# LFFF.net
KiCad netlist of a schematic drawn in Altium Designer
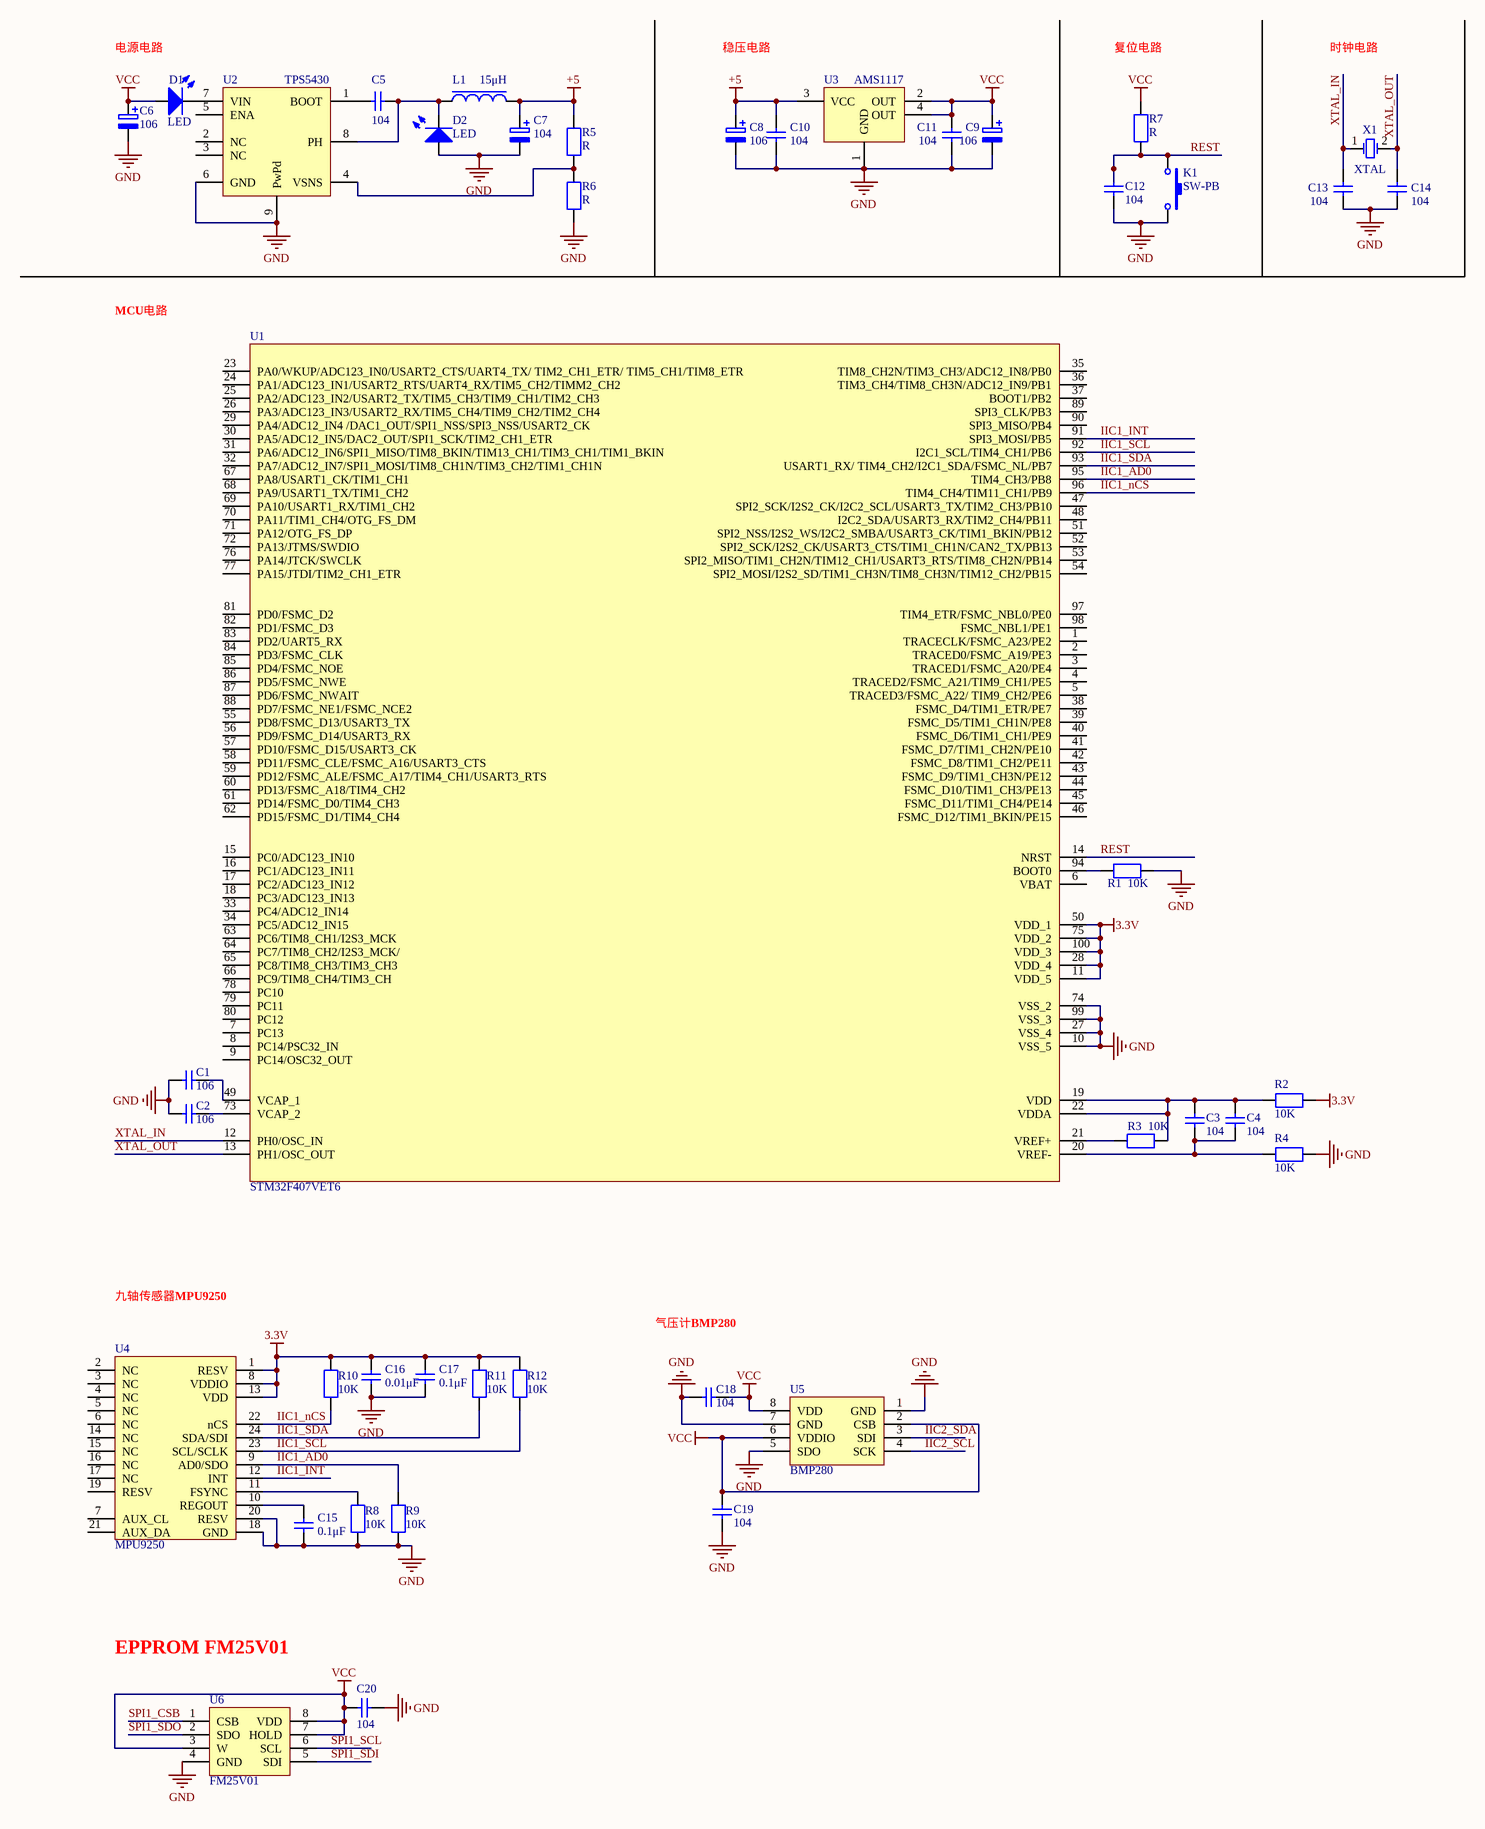
[diagram p0: LFFF.SchDoc]

(export (version "E")
  (design (tool "Eeschema 10.0.6"))
  (components
    (comp (ref "C1") (value "106") (footprint "RC0805") (libsource (lib "LFIF") (part "C")))
    (comp (ref "C2") (value "106") (footprint "RC0805") (libsource (lib "LFIF") (part "C")))
    (comp (ref "C3") (value "104") (footprint "RC0805") (libsource (lib "LFIF") (part "C")))
    (comp (ref "C4") (value "104") (footprint "RC0805") (libsource (lib "LFIF") (part "C")))
    (comp (ref "C5") (value "104") (footprint "RC0805") (libsource (lib "LFIF") (part "C")))
    (comp (ref "C6") (value "106") (footprint "RC0805") (libsource (lib "LFIF") (part "C pol")))
    (comp (ref "C7") (value "104") (footprint "RC0805") (libsource (lib "LFIF") (part "C pol")))
    (comp (ref "C8") (value "106") (footprint "RC0805") (libsource (lib "LFIF") (part "C pol")))
    (comp (ref "C9") (value "106") (footprint "RC0805") (libsource (lib "LFIF") (part "C pol")))
    (comp (ref "C10") (value "104") (footprint "RC0805") (libsource (lib "LFIF") (part "C")))
    (comp (ref "C11") (value "104") (footprint "RC0805") (libsource (lib "LFIF") (part "C")))
    (comp (ref "C12") (value "104") (footprint "RC0805") (libsource (lib "LFIF") (part "C")))
    (comp (ref "C13") (value "104") (footprint "RC0805") (libsource (lib "LFIF") (part "C")))
    (comp (ref "C14") (value "104") (footprint "RC0805") (libsource (lib "LFIF") (part "C")))
    (comp (ref "C15") (value "0.1μF") (footprint "RC0805") (libsource (lib "LFIF") (part "C")))
    (comp (ref "C16") (value "0.01μF") (footprint "RC0805") (libsource (lib "LFIF") (part "C")))
    (comp (ref "C17") (value "0.1μF") (footprint "RC0805") (libsource (lib "LFIF") (part "C")))
    (comp (ref "C18") (value "104") (footprint "RC0805") (libsource (lib "LFIF") (part "C")))
    (comp (ref "C19") (value "104") (footprint "RC0805") (libsource (lib "LFIF") (part "C")))
    (comp (ref "C20") (value "104") (footprint "RC0805") (libsource (lib "LFIF") (part "C")))
    (comp (ref "D1") (value "LED") (footprint "LED") (libsource (lib "LFIF") (part "LED")))
    (comp (ref "D2") (value "LED") (footprint "LED") (libsource (lib "LFIF") (part "LED")))
    (comp (ref "K1") (value "SW-PB") (footprint "SW-PB") (libsource (lib "LFIF") (part "SW-PB")))
    (comp (ref "L1") (value "15μH") (footprint "CD45") (libsource (lib "LFIF") (part "L")))
    (comp (ref "R1") (value "10K") (footprint "RC0805") (libsource (lib "LFIF") (part "R")))
    (comp (ref "R2") (value "10K") (footprint "RC0805") (libsource (lib "LFIF") (part "R")))
    (comp (ref "R3") (value "10K") (footprint "RC0805") (libsource (lib "LFIF") (part "R")))
    (comp (ref "R4") (value "10K") (footprint "RC0805") (libsource (lib "LFIF") (part "R")))
    (comp (ref "R5") (value "R") (footprint "RC0805") (libsource (lib "LFIF") (part "R")))
    (comp (ref "R6") (value "R") (footprint "RC0805") (libsource (lib "LFIF") (part "R")))
    (comp (ref "R7") (value "R") (footprint "RC0805") (libsource (lib "LFIF") (part "R")))
    (comp (ref "R8") (value "10K") (footprint "RC0805") (libsource (lib "LFIF") (part "R")))
    (comp (ref "R9") (value "10K") (footprint "RC0805") (libsource (lib "LFIF") (part "R")))
    (comp (ref "R10") (value "10K") (footprint "RC0805") (libsource (lib "LFIF") (part "R")))
    (comp (ref "R11") (value "10K") (footprint "RC0805") (libsource (lib "LFIF") (part "R")))
    (comp (ref "R12") (value "10K") (footprint "RC0805") (libsource (lib "LFIF") (part "R")))
    (comp (ref "U1")
      (value "STM32F407VET6")
      (footprint "STM32F407VET6")
      (libsource (lib "LFIF") (part "STM32F407VET6"))
    )
    (comp (ref "U2") (value "TPS5430") (footprint "TPS5430") (libsource (lib "LFIF") (part "TPS5430")))
    (comp (ref "U3") (value "AMS1117") (footprint "AMS1117") (libsource (lib "LFIF") (part "AMS1117")))
    (comp (ref "U4") (value "MPU9250") (footprint "MPU9250") (libsource (lib "LFIF") (part "MPU9250")))
    (comp (ref "U5") (value "BMP280") (libsource (lib "LFIF") (part "BMP280")))
    (comp (ref "U6") (value "FM25V01") (footprint "FM25V01") (libsource (lib "LFIF") (part "FM25V01")))
    (comp (ref "X1") (value "XTAL") (footprint "49S-SMD") (libsource (lib "LFIF") (part "XTAL")))
  )
  (nets
    (net (code "1") (name "+5") (class "Default")
      (node (ref "C10") (pin "1") (pintype "passive"))
      (node (ref "C7") (pin "1") (pintype "passive"))
      (node (ref "C8") (pin "1") (pintype "passive"))
      (node (ref "L1") (pin "2") (pintype "passive"))
      (node (ref "R5") (pin "2") (pintype "passive"))
      (node (ref "U3") (pin "3") (pinfunction "VCC_3") (pintype "passive"))
    )
    (net (code "2") (name "/IIC1_AD0") (class "Default")
      (node (ref "R9") (pin "2") (pintype "passive"))
      (node (ref "U1") (pin "95") (pinfunction "TIM4_CH3/PB8_95") (pintype "passive"))
      (node (ref "U4") (pin "9") (pinfunction "AD0/SDO_9") (pintype "passive"))
    )
    (net (code "3") (name "/IIC1_INT") (class "Default")
      (node (ref "U1") (pin "91") (pinfunction "SPI3_MOSI/PB5_91") (pintype "passive"))
      (node (ref "U4") (pin "12") (pinfunction "INT_12") (pintype "passive"))
    )
    (net (code "4") (name "/IIC1_SCL") (class "Default")
      (node (ref "R12") (pin "1") (pintype "passive"))
      (node (ref "U1") (pin "92") (pinfunction "I2C1_SCL/TIM4_CH1/PB6_92") (pintype "passive"))
      (node (ref "U4") (pin "23") (pinfunction "SCL/SCLK_23") (pintype "passive"))
    )
    (net (code "5") (name "/IIC1_SDA") (class "Default")
      (node (ref "R11") (pin "1") (pintype "passive"))
      (node (ref "U1") (pin "93") (pinfunction "USART1_RX/_TIM4_CH2/I2C1_SDA/FSMC_NL/PB7_93") (pintype "passive"))
      (node (ref "U4") (pin "24") (pinfunction "SDA/SDI_24") (pintype "passive"))
    )
    (net (code "6") (name "/IIC1_nCS") (class "Default")
      (node (ref "R10") (pin "1") (pintype "passive"))
      (node (ref "U1") (pin "96") (pinfunction "TIM4_CH4/TIM11_CH1/PB9_96") (pintype "passive"))
      (node (ref "U4") (pin "22") (pinfunction "nCS_22") (pintype "passive"))
    )
    (net (code "7") (name "/IIC2_SCL") (class "Default")
      (node (ref "U5") (pin "4") (pinfunction "SCK_4") (pintype "passive"))
    )
    (net (code "8") (name "/IIC2_SDA") (class "Default")
      (node (ref "U5") (pin "3") (pinfunction "SDI_3") (pintype "passive"))
    )
    (net (code "9") (name "/REST") (class "Default")
      (node (ref "C12") (pin "2") (pintype "passive"))
      (node (ref "K1") (pin "1") (pintype "passive"))
      (node (ref "R7") (pin "1") (pintype "passive"))
      (node (ref "U1") (pin "14") (pinfunction "NRST_14") (pintype "passive"))
    )
    (net (code "10") (name "/SPI1_CSB") (class "Default")
      (node (ref "U6") (pin "1") (pinfunction "CSB_1") (pintype "passive"))
    )
    (net (code "11") (name "/SPI1_SCL") (class "Default")
      (node (ref "U6") (pin "6") (pinfunction "SCL_6") (pintype "passive"))
    )
    (net (code "12") (name "/SPI1_SDI") (class "Default")
      (node (ref "U6") (pin "5") (pinfunction "SDI_5") (pintype "passive"))
    )
    (net (code "13") (name "/SPI1_SDO") (class "Default")
      (node (ref "U6") (pin "2") (pinfunction "SDO_2") (pintype "passive"))
    )
    (net (code "14") (name "/XTAL_IN") (class "Default")
      (node (ref "C13") (pin "2") (pintype "passive"))
      (node (ref "U1") (pin "12") (pinfunction "PH0/OSC_IN_12") (pintype "passive"))
      (node (ref "X1") (pin "1") (pinfunction "IN_1") (pintype "passive"))
    )
    (net (code "15") (name "/XTAL_OUT") (class "Default")
      (node (ref "C14") (pin "2") (pintype "passive"))
      (node (ref "U1") (pin "13") (pinfunction "PH1/OSC_OUT_13") (pintype "passive"))
      (node (ref "X1") (pin "2") (pinfunction "OUT_2") (pintype "passive"))
    )
    (net (code "16") (name "3.3V") (class "Default")
      (node (ref "C16") (pin "2") (pintype "passive"))
      (node (ref "C17") (pin "2") (pintype "passive"))
      (node (ref "R10") (pin "2") (pintype "passive"))
      (node (ref "R11") (pin "2") (pintype "passive"))
      (node (ref "R12") (pin "2") (pintype "passive"))
      (node (ref "R2") (pin "2") (pintype "passive"))
      (node (ref "U1") (pin "100") (pinfunction "VDD_3_100") (pintype "passive"))
      (node (ref "U1") (pin "11") (pinfunction "VDD_5_11") (pintype "passive"))
      (node (ref "U1") (pin "28") (pinfunction "VDD_4_28") (pintype "passive"))
      (node (ref "U1") (pin "50") (pinfunction "VDD_1_50") (pintype "passive"))
      (node (ref "U1") (pin "75") (pinfunction "VDD_2_75") (pintype "passive"))
      (node (ref "U4") (pin "1") (pinfunction "RESV_1") (pintype "passive"))
      (node (ref "U4") (pin "13") (pinfunction "VDD_13") (pintype "passive"))
      (node (ref "U4") (pin "8") (pinfunction "VDDIO_8") (pintype "passive"))
    )
    (net (code "17") (name "GND") (class "Default")
      (node (ref "C1") (pin "1") (pintype "passive"))
      (node (ref "C10") (pin "2") (pintype "passive"))
      (node (ref "C11") (pin "2") (pintype "passive"))
      (node (ref "C12") (pin "1") (pintype "passive"))
      (node (ref "C13") (pin "1") (pintype "passive"))
      (node (ref "C14") (pin "1") (pintype "passive"))
      (node (ref "C15") (pin "1") (pintype "passive"))
      (node (ref "C16") (pin "1") (pintype "passive"))
      (node (ref "C17") (pin "1") (pintype "passive"))
      (node (ref "C18") (pin "1") (pintype "passive"))
      (node (ref "C19") (pin "1") (pintype "passive"))
      (node (ref "C2") (pin "1") (pintype "passive"))
      (node (ref "C20") (pin "2") (pintype "passive"))
      (node (ref "C6") (pin "2") (pintype "passive"))
      (node (ref "C7") (pin "2") (pintype "passive"))
      (node (ref "C8") (pin "2") (pintype "passive"))
      (node (ref "C9") (pin "2") (pintype "passive"))
      (node (ref "D2") (pin "1") (pintype "passive"))
      (node (ref "K1") (pin "2") (pintype "passive"))
      (node (ref "R1") (pin "2") (pintype "passive"))
      (node (ref "R4") (pin "2") (pintype "passive"))
      (node (ref "R6") (pin "1") (pintype "passive"))
      (node (ref "R8") (pin "1") (pintype "passive"))
      (node (ref "R9") (pin "1") (pintype "passive"))
      (node (ref "U1") (pin "10") (pinfunction "VSS_5_10") (pintype "passive"))
      (node (ref "U1") (pin "27") (pinfunction "VSS_4_27") (pintype "passive"))
      (node (ref "U1") (pin "74") (pinfunction "VSS_2_74") (pintype "passive"))
      (node (ref "U1") (pin "99") (pinfunction "VSS_3_99") (pintype "passive"))
      (node (ref "U2") (pin "6") (pinfunction "GND_6") (pintype "passive"))
      (node (ref "U2") (pin "9") (pinfunction "PwPd_9") (pintype "passive"))
      (node (ref "U3") (pin "1") (pinfunction "GND_1") (pintype "passive"))
      (node (ref "U4") (pin "18") (pinfunction "GND_18") (pintype "passive"))
      (node (ref "U4") (pin "20") (pinfunction "RESV_20") (pintype "passive"))
      (node (ref "U5") (pin "1") (pinfunction "GND_1") (pintype "passive"))
      (node (ref "U5") (pin "5") (pinfunction "SDO_5") (pintype "passive"))
      (node (ref "U5") (pin "7") (pinfunction "GND_7") (pintype "passive"))
      (node (ref "U6") (pin "4") (pinfunction "GND_4") (pintype "passive"))
    )
    (net (code "18") (name "Net-(U1-BOOT0)") (class "Default")
      (node (ref "R1") (pin "1") (pintype "passive"))
      (node (ref "U1") (pin "94") (pinfunction "BOOT0_94") (pintype "passive"))
    )
    (net (code "19") (name "Net-(U1-VCAP_1)") (class "Default")
      (node (ref "C1") (pin "2") (pintype "passive"))
      (node (ref "U1") (pin "49") (pinfunction "VCAP_1_49") (pintype "passive"))
    )
    (net (code "20") (name "Net-(U1-VCAP_2)") (class "Default")
      (node (ref "C2") (pin "2") (pintype "passive"))
      (node (ref "U1") (pin "73") (pinfunction "VCAP_2_73") (pintype "passive"))
    )
    (net (code "21") (name "Net-(U1-VDD)") (class "Default")
      (node (ref "C3") (pin "2") (pintype "passive"))
      (node (ref "C4") (pin "2") (pintype "passive"))
      (node (ref "R2") (pin "1") (pintype "passive"))
      (node (ref "R3") (pin "2") (pintype "passive"))
      (node (ref "U1") (pin "19") (pinfunction "VDD_19") (pintype "passive"))
      (node (ref "U1") (pin "22") (pinfunction "VDDA_22") (pintype "passive"))
    )
    (net (code "22") (name "Net-(U1-VREF+)") (class "Default")
      (node (ref "R3") (pin "1") (pintype "passive"))
      (node (ref "U1") (pin "21") (pinfunction "VREF+_21") (pintype "passive"))
    )
    (net (code "23") (name "Net-(U1-VREF-)") (class "Default")
      (node (ref "C3") (pin "1") (pintype "passive"))
      (node (ref "C4") (pin "1") (pintype "passive"))
      (node (ref "R4") (pin "1") (pintype "passive"))
      (node (ref "U1") (pin "20") (pinfunction "VREF-_20") (pintype "passive"))
    )
    (net (code "24") (name "Net-(U2-BOOT)") (class "Default")
      (node (ref "C5") (pin "1") (pintype "passive"))
      (node (ref "U2") (pin "1") (pinfunction "BOOT_1") (pintype "passive"))
    )
    (net (code "25") (name "Net-(U2-PH)") (class "Default")
      (node (ref "C5") (pin "2") (pintype "passive"))
      (node (ref "D2") (pin "2") (pintype "passive"))
      (node (ref "L1") (pin "1") (pintype "passive"))
      (node (ref "U2") (pin "8") (pinfunction "PH_8") (pintype "passive"))
    )
    (net (code "26") (name "Net-(U2-VIN)") (class "Default")
      (node (ref "D1") (pin "2") (pintype "passive"))
      (node (ref "U2") (pin "7") (pinfunction "VIN_7") (pintype "passive"))
    )
    (net (code "27") (name "Net-(U2-VSNS)") (class "Default")
      (node (ref "R5") (pin "1") (pintype "passive"))
      (node (ref "R6") (pin "2") (pintype "passive"))
      (node (ref "U2") (pin "4") (pinfunction "VSNS_4") (pintype "passive"))
    )
    (net (code "28") (name "Net-(U4-FSYNC)") (class "Default")
      (node (ref "R8") (pin "2") (pintype "passive"))
      (node (ref "U4") (pin "11") (pinfunction "FSYNC_11") (pintype "passive"))
    )
    (net (code "29") (name "Net-(U4-REGOUT)") (class "Default")
      (node (ref "C15") (pin "2") (pintype "passive"))
      (node (ref "U4") (pin "10") (pinfunction "REGOUT_10") (pintype "passive"))
    )
    (net (code "30") (name "VCC") (class "Default")
      (node (ref "C11") (pin "1") (pintype "passive"))
      (node (ref "C18") (pin "2") (pintype "passive"))
      (node (ref "C19") (pin "2") (pintype "passive"))
      (node (ref "C20") (pin "1") (pintype "passive"))
      (node (ref "C6") (pin "1") (pintype "passive"))
      (node (ref "C9") (pin "1") (pintype "passive"))
      (node (ref "D1") (pin "1") (pintype "passive"))
      (node (ref "R7") (pin "2") (pintype "passive"))
      (node (ref "U3") (pin "2") (pinfunction "OUT_2") (pintype "passive"))
      (node (ref "U3") (pin "4") (pinfunction "OUT_4") (pintype "passive"))
      (node (ref "U5") (pin "2") (pinfunction "CSB_2") (pintype "passive"))
      (node (ref "U5") (pin "6") (pinfunction "VDDIO_6") (pintype "passive"))
      (node (ref "U5") (pin "8") (pinfunction "VDD_8") (pintype "passive"))
      (node (ref "U6") (pin "3") (pinfunction "W_3") (pintype "passive"))
      (node (ref "U6") (pin "7") (pinfunction "HOLD_7") (pintype "passive"))
      (node (ref "U6") (pin "8") (pinfunction "VDD_8") (pintype "passive"))
    )
    (net (code "31") (name "unconnected-(U1-BOOT1{slash}PB2-Pad37)") (class "Default")
      (node (ref "U1") (pin "37") (pinfunction "BOOT1/PB2_37") (pintype "passive"))
    )
    (net (code "32") (name "unconnected-(U1-FSMC_D4{slash}TIM1_ETR{slash}PE7-Pad38)") (class "Default")
      (node (ref "U1") (pin "38") (pinfunction "FSMC_D4/TIM1_ETR/PE7_38") (pintype "passive"))
    )
    (net (code "33") (name "unconnected-(U1-FSMC_D5{slash}TIM1_CH1N{slash}PE8-Pad39)") (class "Default")
      (node (ref "U1") (pin "39") (pinfunction "FSMC_D5/TIM1_CH1N/PE8_39") (pintype "passive"))
    )
    (net (code "34") (name "unconnected-(U1-FSMC_D6{slash}TIM1_CH1{slash}PE9-Pad40)") (class "Default")
      (node (ref "U1") (pin "40") (pinfunction "FSMC_D6/TIM1_CH1/PE9_40") (pintype "passive"))
    )
    (net (code "35") (name "unconnected-(U1-FSMC_D7{slash}TIM1_CH2N{slash}PE10-Pad41)") (class "Default")
      (node (ref "U1") (pin "41") (pinfunction "FSMC_D7/TIM1_CH2N/PE10_41") (pintype "passive"))
    )
    (net (code "36") (name "unconnected-(U1-FSMC_D8{slash}TIM1_CH2{slash}PE11-Pad42)") (class "Default")
      (node (ref "U1") (pin "42") (pinfunction "FSMC_D8/TIM1_CH2/PE11_42") (pintype "passive"))
    )
    (net (code "37") (name "unconnected-(U1-FSMC_D9{slash}TIM1_CH3N{slash}PE12-Pad43)") (class "Default")
      (node (ref "U1") (pin "43") (pinfunction "FSMC_D9/TIM1_CH3N/PE12_43") (pintype "passive"))
    )
    (net (code "38") (name "unconnected-(U1-FSMC_D10{slash}TIM1_CH3{slash}PE13-Pad44)") (class "Default")
      (node (ref "U1") (pin "44") (pinfunction "FSMC_D10/TIM1_CH3/PE13_44") (pintype "passive"))
    )
    (net (code "39") (name "unconnected-(U1-FSMC_D11{slash}TIM1_CH4{slash}PE14-Pad45)") (class "Default")
      (node (ref "U1") (pin "45") (pinfunction "FSMC_D11/TIM1_CH4/PE14_45") (pintype "passive"))
    )
    (net (code "40") (name "unconnected-(U1-FSMC_D12{slash}TIM1_BKIN{slash}PE15-Pad46)") (class "Default")
      (node (ref "U1") (pin "46") (pinfunction "FSMC_D12/TIM1_BKIN/PE15_46") (pintype "passive"))
    )
    (net (code "41") (name "unconnected-(U1-FSMC_NBL1{slash}PE1-Pad98)") (class "Default")
      (node (ref "U1") (pin "98") (pinfunction "FSMC_NBL1/PE1_98") (pintype "passive"))
    )
    (net (code "42") (name "unconnected-(U1-I2C2_SDA{slash}USART3_RX{slash}TIM2_CH4{slash}PB11-Pad48)") (class "Default")
      (node (ref "U1") (pin "48") (pinfunction "I2C2_SDA/USART3_RX/TIM2_CH4/PB11_48") (pintype "passive"))
    )
    (net (code "43") (name "unconnected-(U1-PA0{slash}WKUP{slash}ADC123_IN0{slash}USART2_CTS{slash}UART4_TX{slash}_TIM2_CH1_ETR{slash}_TIM5_CH1{slash}TIM8_ETR-Pad23)") (class "Default")
      (node (ref "U1") (pin "23") (pinfunction "PA0/WKUP/ADC123_IN0/USART2_CTS/UART4_TX/_TIM2_CH1_ETR/_TIM5_CH1/TIM8_ETR_23") (pintype "passive"))
    )
    (net (code "44") (name "unconnected-(U1-PA1{slash}ADC123_IN1{slash}USART2_RTS{slash}UART4_RX{slash}TIM5_CH2{slash}TIMM2_CH2-Pad24)") (class "Default")
      (node (ref "U1") (pin "24") (pinfunction "PA1/ADC123_IN1/USART2_RTS/UART4_RX/TIM5_CH2/TIMM2_CH2_24") (pintype "passive"))
    )
    (net (code "45") (name "unconnected-(U1-PA2{slash}ADC123_IN2{slash}USART2_TX{slash}TIM5_CH3{slash}TIM9_CH1{slash}TIM2_CH3-Pad25)") (class "Default")
      (node (ref "U1") (pin "25") (pinfunction "PA2/ADC123_IN2/USART2_TX/TIM5_CH3/TIM9_CH1/TIM2_CH3_25") (pintype "passive"))
    )
    (net (code "46") (name "unconnected-(U1-PA3{slash}ADC123_IN3{slash}USART2_RX{slash}TIM5_CH4{slash}TIM9_CH2{slash}TIM2_CH4-Pad26)") (class "Default")
      (node (ref "U1") (pin "26") (pinfunction "PA3/ADC123_IN3/USART2_RX/TIM5_CH4/TIM9_CH2/TIM2_CH4_26") (pintype "passive"))
    )
    (net (code "47") (name "unconnected-(U1-PA4{slash}ADC12_IN4_{slash}DAC1_OUT{slash}SPI1_NSS{slash}SPI3_NSS{slash}USART2_CK-Pad29)") (class "Default")
      (node (ref "U1") (pin "29") (pinfunction "PA4/ADC12_IN4_/DAC1_OUT/SPI1_NSS/SPI3_NSS/USART2_CK_29") (pintype "passive"))
    )
    (net (code "48") (name "unconnected-(U1-PA5{slash}ADC12_IN5{slash}DAC2_OUT{slash}SPI1_SCK{slash}TIM2_CH1_ETR-Pad30)") (class "Default")
      (node (ref "U1") (pin "30") (pinfunction "PA5/ADC12_IN5/DAC2_OUT/SPI1_SCK/TIM2_CH1_ETR_30") (pintype "passive"))
    )
    (net (code "49") (name "unconnected-(U1-PA6{slash}ADC12_IN6{slash}SPI1_MISO{slash}TIM8_BKIN{slash}TIM13_CH1{slash}TIM3_CH1{slash}TIM1_BKIN-Pad31)") (class "Default")
      (node (ref "U1") (pin "31") (pinfunction "PA6/ADC12_IN6/SPI1_MISO/TIM8_BKIN/TIM13_CH1/TIM3_CH1/TIM1_BKIN_31") (pintype "passive"))
    )
    (net (code "50") (name "unconnected-(U1-PA7{slash}ADC12_IN7{slash}SPI1_MOSI{slash}TIM8_CH1N{slash}TIM3_CH2{slash}TIM1_CH1N-Pad32)") (class "Default")
      (node (ref "U1") (pin "32") (pinfunction "PA7/ADC12_IN7/SPI1_MOSI/TIM8_CH1N/TIM3_CH2/TIM1_CH1N_32") (pintype "passive"))
    )
    (net (code "51") (name "unconnected-(U1-PA8{slash}USART1_CK{slash}TIM1_CH1-Pad67)") (class "Default")
      (node (ref "U1") (pin "67") (pinfunction "PA8/USART1_CK/TIM1_CH1_67") (pintype "passive"))
    )
    (net (code "52") (name "unconnected-(U1-PA9{slash}USART1_TX{slash}TIM1_CH2-Pad68)") (class "Default")
      (node (ref "U1") (pin "68") (pinfunction "PA9/USART1_TX/TIM1_CH2_68") (pintype "passive"))
    )
    (net (code "53") (name "unconnected-(U1-PA10{slash}USART1_RX{slash}TIM1_CH2-Pad69)") (class "Default")
      (node (ref "U1") (pin "69") (pinfunction "PA10/USART1_RX/TIM1_CH2_69") (pintype "passive"))
    )
    (net (code "54") (name "unconnected-(U1-PA11{slash}TIM1_CH4{slash}OTG_FS_DM-Pad70)") (class "Default")
      (node (ref "U1") (pin "70") (pinfunction "PA11/TIM1_CH4/OTG_FS_DM_70") (pintype "passive"))
    )
    (net (code "55") (name "unconnected-(U1-PA12{slash}OTG_FS_DP-Pad71)") (class "Default")
      (node (ref "U1") (pin "71") (pinfunction "PA12/OTG_FS_DP_71") (pintype "passive"))
    )
    (net (code "56") (name "unconnected-(U1-PA13{slash}JTMS{slash}SWDIO-Pad72)") (class "Default")
      (node (ref "U1") (pin "72") (pinfunction "PA13/JTMS/SWDIO_72") (pintype "passive"))
    )
    (net (code "57") (name "unconnected-(U1-PA14{slash}JTCK{slash}SWCLK-Pad76)") (class "Default")
      (node (ref "U1") (pin "76") (pinfunction "PA14/JTCK/SWCLK_76") (pintype "passive"))
    )
    (net (code "58") (name "unconnected-(U1-PA15{slash}JTDI{slash}TIM2_CH1_ETR-Pad77)") (class "Default")
      (node (ref "U1") (pin "77") (pinfunction "PA15/JTDI/TIM2_CH1_ETR_77") (pintype "passive"))
    )
    (net (code "59") (name "unconnected-(U1-PC0{slash}ADC123_IN10-Pad15)") (class "Default")
      (node (ref "U1") (pin "15") (pinfunction "PC0/ADC123_IN10_15") (pintype "passive"))
    )
    (net (code "60") (name "unconnected-(U1-PC1{slash}ADC123_IN11-Pad16)") (class "Default")
      (node (ref "U1") (pin "16") (pinfunction "PC1/ADC123_IN11_16") (pintype "passive"))
    )
    (net (code "61") (name "unconnected-(U1-PC2{slash}ADC123_IN12-Pad17)") (class "Default")
      (node (ref "U1") (pin "17") (pinfunction "PC2/ADC123_IN12_17") (pintype "passive"))
    )
    (net (code "62") (name "unconnected-(U1-PC3{slash}ADC123_IN13-Pad18)") (class "Default")
      (node (ref "U1") (pin "18") (pinfunction "PC3/ADC123_IN13_18") (pintype "passive"))
    )
    (net (code "63") (name "unconnected-(U1-PC4{slash}ADC12_IN14-Pad33)") (class "Default")
      (node (ref "U1") (pin "33") (pinfunction "PC4/ADC12_IN14_33") (pintype "passive"))
    )
    (net (code "64") (name "unconnected-(U1-PC5{slash}ADC12_IN15-Pad34)") (class "Default")
      (node (ref "U1") (pin "34") (pinfunction "PC5/ADC12_IN15_34") (pintype "passive"))
    )
    (net (code "65") (name "unconnected-(U1-PC6{slash}TIM8_CH1{slash}I2S3_MCK-Pad63)") (class "Default")
      (node (ref "U1") (pin "63") (pinfunction "PC6/TIM8_CH1/I2S3_MCK_63") (pintype "passive"))
    )
    (net (code "66") (name "unconnected-(U1-PC7{slash}TIM8_CH2{slash}I2S3_MCK{slash}-Pad64)") (class "Default")
      (node (ref "U1") (pin "64") (pinfunction "PC7/TIM8_CH2/I2S3_MCK/_64") (pintype "passive"))
    )
    (net (code "67") (name "unconnected-(U1-PC8{slash}TIM8_CH3{slash}TIM3_CH3-Pad65)") (class "Default")
      (node (ref "U1") (pin "65") (pinfunction "PC8/TIM8_CH3/TIM3_CH3_65") (pintype "passive"))
    )
    (net (code "68") (name "unconnected-(U1-PC9{slash}TIM8_CH4{slash}TIM3_CH-Pad66)") (class "Default")
      (node (ref "U1") (pin "66") (pinfunction "PC9/TIM8_CH4/TIM3_CH_66") (pintype "passive"))
    )
    (net (code "69") (name "unconnected-(U1-PC10-Pad78)") (class "Default")
      (node (ref "U1") (pin "78") (pinfunction "PC10_78") (pintype "passive"))
    )
    (net (code "70") (name "unconnected-(U1-PC11-Pad79)") (class "Default")
      (node (ref "U1") (pin "79") (pinfunction "PC11_79") (pintype "passive"))
    )
    (net (code "71") (name "unconnected-(U1-PC12-Pad80)") (class "Default")
      (node (ref "U1") (pin "80") (pinfunction "PC12_80") (pintype "passive"))
    )
    (net (code "72") (name "unconnected-(U1-PC13-Pad7)") (class "Default")
      (node (ref "U1") (pin "7") (pinfunction "PC13_7") (pintype "passive"))
    )
    (net (code "73") (name "unconnected-(U1-PC14{slash}OSC32_OUT-Pad9)") (class "Default")
      (node (ref "U1") (pin "9") (pinfunction "PC14/OSC32_OUT_9") (pintype "passive"))
    )
    (net (code "74") (name "unconnected-(U1-PC14{slash}PSC32_IN-Pad8)") (class "Default")
      (node (ref "U1") (pin "8") (pinfunction "PC14/PSC32_IN_8") (pintype "passive"))
    )
    (net (code "75") (name "unconnected-(U1-PD0{slash}FSMC_D2-Pad81)") (class "Default")
      (node (ref "U1") (pin "81") (pinfunction "PD0/FSMC_D2_81") (pintype "passive"))
    )
    (net (code "76") (name "unconnected-(U1-PD1{slash}FSMC_D3-Pad82)") (class "Default")
      (node (ref "U1") (pin "82") (pinfunction "PD1/FSMC_D3_82") (pintype "passive"))
    )
    (net (code "77") (name "unconnected-(U1-PD2{slash}UART5_RX-Pad83)") (class "Default")
      (node (ref "U1") (pin "83") (pinfunction "PD2/UART5_RX_83") (pintype "passive"))
    )
    (net (code "78") (name "unconnected-(U1-PD3{slash}FSMC_CLK-Pad84)") (class "Default")
      (node (ref "U1") (pin "84") (pinfunction "PD3/FSMC_CLK_84") (pintype "passive"))
    )
    (net (code "79") (name "unconnected-(U1-PD4{slash}FSMC_NOE-Pad85)") (class "Default")
      (node (ref "U1") (pin "85") (pinfunction "PD4/FSMC_NOE_85") (pintype "passive"))
    )
    (net (code "80") (name "unconnected-(U1-PD5{slash}FSMC_NWE-Pad86)") (class "Default")
      (node (ref "U1") (pin "86") (pinfunction "PD5/FSMC_NWE_86") (pintype "passive"))
    )
    (net (code "81") (name "unconnected-(U1-PD6{slash}FSMC_NWAIT-Pad87)") (class "Default")
      (node (ref "U1") (pin "87") (pinfunction "PD6/FSMC_NWAIT_87") (pintype "passive"))
    )
    (net (code "82") (name "unconnected-(U1-PD7{slash}FSMC_NE1{slash}FSMC_NCE2-Pad88)") (class "Default")
      (node (ref "U1") (pin "88") (pinfunction "PD7/FSMC_NE1/FSMC_NCE2_88") (pintype "passive"))
    )
    (net (code "83") (name "unconnected-(U1-PD8{slash}FSMC_D13{slash}USART3_TX-Pad55)") (class "Default")
      (node (ref "U1") (pin "55") (pinfunction "PD8/FSMC_D13/USART3_TX_55") (pintype "passive"))
    )
    (net (code "84") (name "unconnected-(U1-PD9{slash}FSMC_D14{slash}USART3_RX-Pad56)") (class "Default")
      (node (ref "U1") (pin "56") (pinfunction "PD9/FSMC_D14/USART3_RX_56") (pintype "passive"))
    )
    (net (code "85") (name "unconnected-(U1-PD10{slash}FSMC_D15{slash}USART3_CK-Pad57)") (class "Default")
      (node (ref "U1") (pin "57") (pinfunction "PD10/FSMC_D15/USART3_CK_57") (pintype "passive"))
    )
    (net (code "86") (name "unconnected-(U1-PD11{slash}FSMC_CLE{slash}FSMC_A16{slash}USART3_CTS-Pad58)") (class "Default")
      (node (ref "U1") (pin "58") (pinfunction "PD11/FSMC_CLE/FSMC_A16/USART3_CTS_58") (pintype "passive"))
    )
    (net (code "87") (name "unconnected-(U1-PD12{slash}FSMC_ALE{slash}FSMC_A17{slash}TIM4_CH1{slash}USART3_RTS-Pad59)") (class "Default")
      (node (ref "U1") (pin "59") (pinfunction "PD12/FSMC_ALE/FSMC_A17/TIM4_CH1/USART3_RTS_59") (pintype "passive"))
    )
    (net (code "88") (name "unconnected-(U1-PD13{slash}FSMC_A18{slash}TIM4_CH2-Pad60)") (class "Default")
      (node (ref "U1") (pin "60") (pinfunction "PD13/FSMC_A18/TIM4_CH2_60") (pintype "passive"))
    )
    (net (code "89") (name "unconnected-(U1-PD14{slash}FSMC_D0{slash}TIM4_CH3-Pad61)") (class "Default")
      (node (ref "U1") (pin "61") (pinfunction "PD14/FSMC_D0/TIM4_CH3_61") (pintype "passive"))
    )
    (net (code "90") (name "unconnected-(U1-PD15{slash}FSMC_D1{slash}TIM4_CH4-Pad62)") (class "Default")
      (node (ref "U1") (pin "62") (pinfunction "PD15/FSMC_D1/TIM4_CH4_62") (pintype "passive"))
    )
    (net (code "91") (name "unconnected-(U1-SPI2_MISO{slash}TIM1_CH2N{slash}TIM12_CH1{slash}USART3_RTS{slash}TIM8_CH2N{slash}PB14-Pad53)") (class "Default")
      (node (ref "U1") (pin "53") (pinfunction "SPI2_MISO/TIM1_CH2N/TIM12_CH1/USART3_RTS/TIM8_CH2N/PB14_53") (pintype "passive"))
    )
    (net (code "92") (name "unconnected-(U1-SPI2_MOSI{slash}I2S2_SD{slash}TIM1_CH3N{slash}TIM8_CH3N{slash}TIM12_CH2{slash}PB15-Pad54)") (class "Default")
      (node (ref "U1") (pin "54") (pinfunction "SPI2_MOSI/I2S2_SD/TIM1_CH3N/TIM8_CH3N/TIM12_CH2/PB15_54") (pintype "passive"))
    )
    (net (code "93") (name "unconnected-(U1-SPI2_NSS{slash}I2S2_WS{slash}I2C2_SMBA{slash}USART3_CK{slash}TIM1_BKIN{slash}PB12-Pad51)") (class "Default")
      (node (ref "U1") (pin "51") (pinfunction "SPI2_NSS/I2S2_WS/I2C2_SMBA/USART3_CK/TIM1_BKIN/PB12_51") (pintype "passive"))
    )
    (net (code "94") (name "unconnected-(U1-SPI2_SCK{slash}I2S2_CK{slash}I2C2_SCL{slash}USART3_TX{slash}TIM2_CH3{slash}PB10-Pad47)") (class "Default")
      (node (ref "U1") (pin "47") (pinfunction "SPI2_SCK/I2S2_CK/I2C2_SCL/USART3_TX/TIM2_CH3/PB10_47") (pintype "passive"))
    )
    (net (code "95") (name "unconnected-(U1-SPI2_SCK{slash}I2S2_CK{slash}USART3_CTS{slash}TIM1_CH1N{slash}CAN2_TX{slash}PB13-Pad52)") (class "Default")
      (node (ref "U1") (pin "52") (pinfunction "SPI2_SCK/I2S2_CK/USART3_CTS/TIM1_CH1N/CAN2_TX/PB13_52") (pintype "passive"))
    )
    (net (code "96") (name "unconnected-(U1-SPI3_CLK{slash}PB3-Pad89)") (class "Default")
      (node (ref "U1") (pin "89") (pinfunction "SPI3_CLK/PB3_89") (pintype "passive"))
    )
    (net (code "97") (name "unconnected-(U1-SPI3_MISO{slash}PB4-Pad90)") (class "Default")
      (node (ref "U1") (pin "90") (pinfunction "SPI3_MISO/PB4_90") (pintype "passive"))
    )
    (net (code "98") (name "unconnected-(U1-TIM3_CH4{slash}TIM8_CH3N{slash}ADC12_IN9{slash}PB1-Pad36)") (class "Default")
      (node (ref "U1") (pin "36") (pinfunction "TIM3_CH4/TIM8_CH3N/ADC12_IN9/PB1_36") (pintype "passive"))
    )
    (net (code "99") (name "unconnected-(U1-TIM4_ETR{slash}FSMC_NBL0{slash}PE0-Pad97)") (class "Default")
      (node (ref "U1") (pin "97") (pinfunction "TIM4_ETR/FSMC_NBL0/PE0_97") (pintype "passive"))
    )
    (net (code "100") (name "unconnected-(U1-TIM8_CH2N{slash}TIM3_CH3{slash}ADC12_IN8{slash}PB0-Pad35)") (class "Default")
      (node (ref "U1") (pin "35") (pinfunction "TIM8_CH2N/TIM3_CH3/ADC12_IN8/PB0_35") (pintype "passive"))
    )
    (net (code "101") (name "unconnected-(U1-TRACECLK{slash}FSMC_A23{slash}PE2-Pad1)") (class "Default")
      (node (ref "U1") (pin "1") (pinfunction "TRACECLK/FSMC_A23/PE2_1") (pintype "passive"))
    )
    (net (code "102") (name "unconnected-(U1-TRACED0{slash}FSMC_A19{slash}PE3-Pad2)") (class "Default")
      (node (ref "U1") (pin "2") (pinfunction "TRACED0/FSMC_A19/PE3_2") (pintype "passive"))
    )
    (net (code "103") (name "unconnected-(U1-TRACED1{slash}FSMC_A20{slash}PE4-Pad3)") (class "Default")
      (node (ref "U1") (pin "3") (pinfunction "TRACED1/FSMC_A20/PE4_3") (pintype "passive"))
    )
    (net (code "104") (name "unconnected-(U1-TRACED2{slash}FSMC_A21{slash}TIM9_CH1{slash}PE5-Pad4)") (class "Default")
      (node (ref "U1") (pin "4") (pinfunction "TRACED2/FSMC_A21/TIM9_CH1/PE5_4") (pintype "passive"))
    )
    (net (code "105") (name "unconnected-(U1-TRACED3{slash}FSMC_A22{slash}_TIM9_CH2{slash}PE6-Pad5)") (class "Default")
      (node (ref "U1") (pin "5") (pinfunction "TRACED3/FSMC_A22/_TIM9_CH2/PE6_5") (pintype "passive"))
    )
    (net (code "106") (name "unconnected-(U1-VBAT-Pad6)") (class "Default")
      (node (ref "U1") (pin "6") (pinfunction "VBAT_6") (pintype "passive"))
    )
    (net (code "107") (name "unconnected-(U2-ENA-Pad5)") (class "Default")
      (node (ref "U2") (pin "5") (pinfunction "ENA_5") (pintype "passive"))
    )
    (net (code "108") (name "unconnected-(U2-NC-Pad2)") (class "Default")
      (node (ref "U2") (pin "2") (pinfunction "NC_2") (pintype "passive"))
    )
    (net (code "109") (name "unconnected-(U2-NC-Pad3)") (class "Default")
      (node (ref "U2") (pin "3") (pinfunction "NC_3") (pintype "passive"))
    )
    (net (code "110") (name "unconnected-(U4-AUX_CL-Pad7)") (class "Default")
      (node (ref "U4") (pin "7") (pinfunction "AUX_CL_7") (pintype "passive"))
    )
    (net (code "111") (name "unconnected-(U4-AUX_DA-Pad21)") (class "Default")
      (node (ref "U4") (pin "21") (pinfunction "AUX_DA_21") (pintype "passive"))
    )
    (net (code "112") (name "unconnected-(U4-NC-Pad2)") (class "Default")
      (node (ref "U4") (pin "2") (pinfunction "NC_2") (pintype "passive"))
    )
    (net (code "113") (name "unconnected-(U4-NC-Pad3)") (class "Default")
      (node (ref "U4") (pin "3") (pinfunction "NC_3") (pintype "passive"))
    )
    (net (code "114") (name "unconnected-(U4-NC-Pad4)") (class "Default")
      (node (ref "U4") (pin "4") (pinfunction "NC_4") (pintype "passive"))
    )
    (net (code "115") (name "unconnected-(U4-NC-Pad5)") (class "Default")
      (node (ref "U4") (pin "5") (pinfunction "NC_5") (pintype "passive"))
    )
    (net (code "116") (name "unconnected-(U4-NC-Pad6)") (class "Default")
      (node (ref "U4") (pin "6") (pinfunction "NC_6") (pintype "passive"))
    )
    (net (code "117") (name "unconnected-(U4-NC-Pad14)") (class "Default")
      (node (ref "U4") (pin "14") (pinfunction "NC_14") (pintype "passive"))
    )
    (net (code "118") (name "unconnected-(U4-NC-Pad15)") (class "Default")
      (node (ref "U4") (pin "15") (pinfunction "NC_15") (pintype "passive"))
    )
    (net (code "119") (name "unconnected-(U4-NC-Pad16)") (class "Default")
      (node (ref "U4") (pin "16") (pinfunction "NC_16") (pintype "passive"))
    )
    (net (code "120") (name "unconnected-(U4-NC-Pad17)") (class "Default")
      (node (ref "U4") (pin "17") (pinfunction "NC_17") (pintype "passive"))
    )
    (net (code "121") (name "unconnected-(U4-RESV-Pad19)") (class "Default")
      (node (ref "U4") (pin "19") (pinfunction "RESV_19") (pintype "passive"))
    )
  )
)
